# acdcconverter.net
KiCad netlist of a schematic drawn in EAGLE
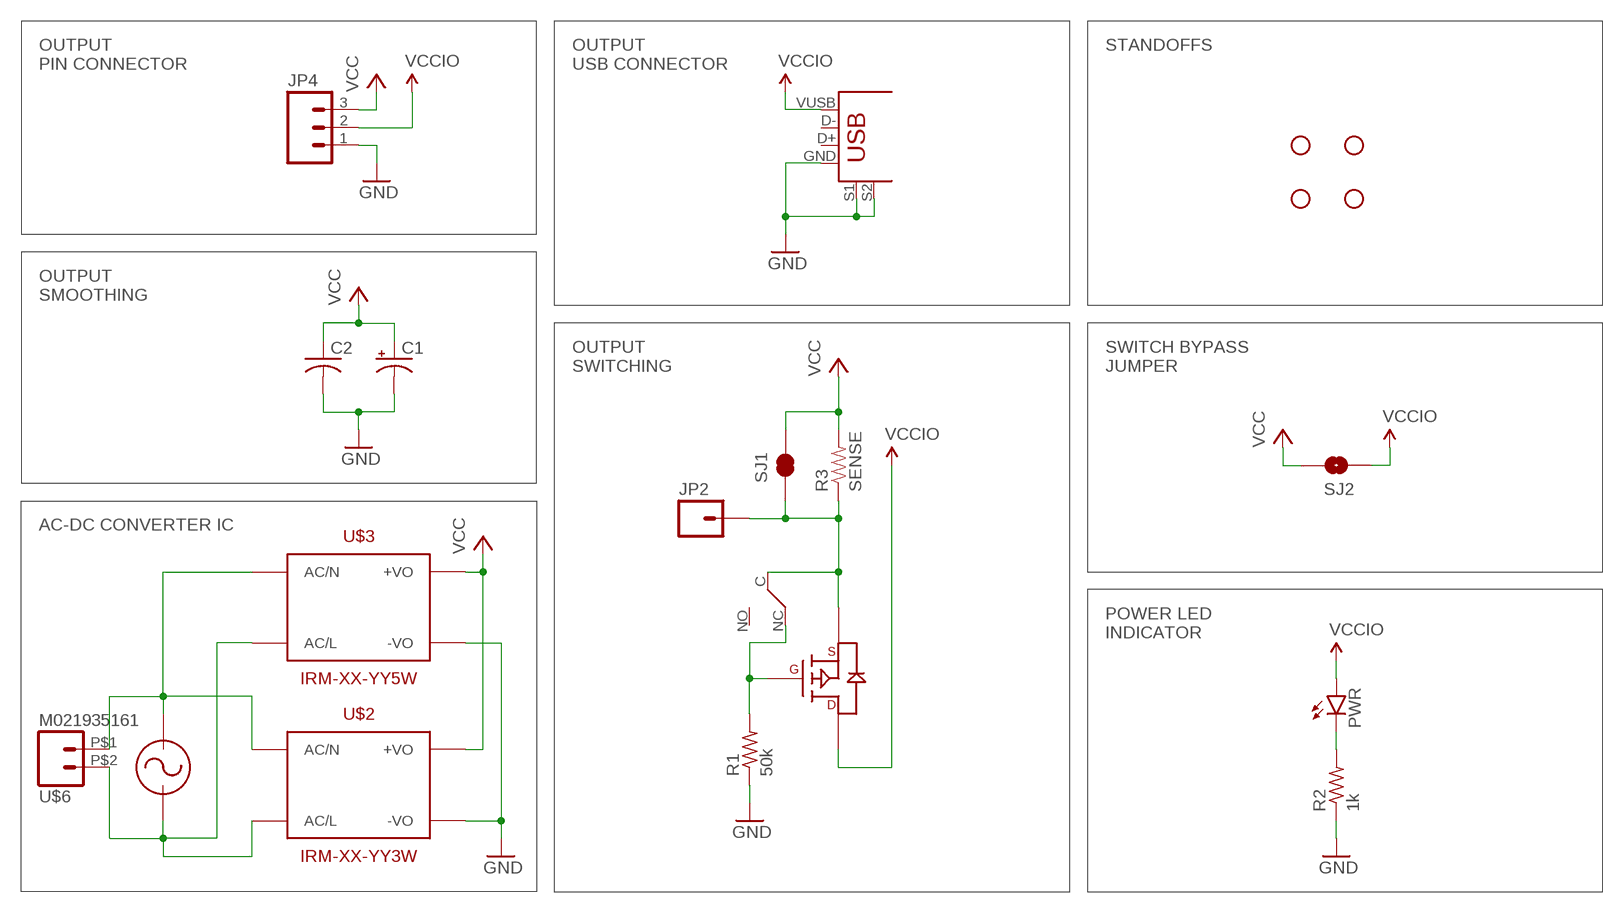
[diagram p0: schematic, sheet 1]

(export (version "E")
  (design (tool "Eeschema 10.0.6"))
  (components
    (comp (ref "C1")
      (value "CPOL-USE2-5")
      (footprint "eagle-import:E2-5")
      (libsource (lib "eagle-import") (part "CPOL-USE2-5"))
    )
    (comp (ref "C2")
      (value "C-USC0603")
      (footprint "eagle-import:C0603")
      (libsource (lib "eagle-import") (part "C-USC0603"))
    )
    (comp (ref "JP2")
      (value "M01PTH")
      (footprint "eagle-import:1X01")
      (libsource (lib "eagle-import") (part "M01PTH"))
    )
    (comp (ref "JP4")
      (value "M03PTH")
      (footprint "eagle-import:1X03")
      (libsource (lib "eagle-import") (part "M03PTH"))
    )
    (comp (ref "PWR")
      (value "LED0603")
      (footprint "eagle-import:LED-0603")
      (libsource (lib "eagle-import") (part "LED0603"))
    )
    (comp (ref "R1")
      (value "50k")
      (footprint "eagle-import:R0603")
      (libsource (lib "eagle-import") (part "R-US_R0603"))
    )
    (comp (ref "R2")
      (value "1k")
      (footprint "eagle-import:R0603")
      (libsource (lib "eagle-import") (part "R-US_R0603"))
    )
    (comp (ref "R3")
      (value "SENSE")
      (footprint "eagle-import:0805")
      (libsource (lib "eagle-import") (part "RESISTOR0805-RES"))
    )
    (comp (ref "SJ1")
      (value "JUMPER-PAD-2-NC_BY_TRACE")
      (footprint "eagle-import:PAD-JUMPER-2-NC_BY_TRACE_YES_SILK")
      (libsource (lib "eagle-import") (part "JUMPER-PAD-2-NC_BY_TRACE"))
    )
    (comp (ref "SJ2")
      (value "SOLDERJUMPERNO")
      (footprint "eagle-import:SJ_2S-NO")
      (libsource (lib "eagle-import") (part "SOLDERJUMPERNO"))
    )
    (comp (ref "STANDOFF1")
      (value "STAND-OFF")
      (footprint "eagle-import:STAND-OFF")
      (libsource (lib "eagle-import") (part "STAND-OFF"))
    )
    (comp (ref "STANDOFF2")
      (value "STAND-OFF")
      (footprint "eagle-import:STAND-OFF")
      (libsource (lib "eagle-import") (part "STAND-OFF"))
    )
    (comp (ref "STANDOFF3")
      (value "STAND-OFF")
      (footprint "eagle-import:STAND-OFF")
      (libsource (lib "eagle-import") (part "STAND-OFF"))
    )
    (comp (ref "STANDOFF4")
      (value "STAND-OFF")
      (footprint "eagle-import:STAND-OFF")
      (libsource (lib "eagle-import") (part "STAND-OFF"))
    )
    (comp (ref "U$1")
      (value "AC-CONNECTOR770W-X2")
      (footprint "eagle-import:770W-X2")
      (libsource (lib "eagle-import") (part "AC-CONNECTOR770W-X2"))
    )
    (comp (ref "U$2")
      (value "IRM-XX-YY3W")
      (footprint "eagle-import:IRM-03-YY")
      (libsource (lib "eagle-import") (part "IRM-XX-YY3W"))
    )
    (comp (ref "U$3")
      (value "IRM-XX-YY5W")
      (footprint "eagle-import:IRM-05-YY")
      (libsource (lib "eagle-import") (part "IRM-XX-YY5W"))
    )
    (comp (ref "U$5")
      (value "SWITCH-SPDT")
      (footprint "eagle-import:SWITCH-1825232-1")
      (libsource (lib "eagle-import") (part "SWITCH-SPDT"))
    )
    (comp (ref "U$6")
      (value "M021935161")
      (footprint "eagle-import:M02-1935161")
      (libsource (lib "eagle-import") (part "M021935161"))
    )
    (comp (ref "U$7")
      (value "USB-FEMALE")
      (footprint "eagle-import:FOXCONN-113N-USB-A-FEMALE")
      (libsource (lib "eagle-import") (part "USB-FEMALE"))
    )
    (comp (ref "U$8")
      (value "MOSFET-PDMG2305UX")
      (footprint "eagle-import:SOT23-3")
      (libsource (lib "eagle-import") (part "MOSFET-PDMG2305UX"))
    )
  )
  (nets
    (net (code "1") (name "GND") (class "Default")
      (node (ref "C1") (pin "-") (pinfunction "-_-") (pintype "passive"))
      (node (ref "C2") (pin "2") (pinfunction "2_2") (pintype "passive"))
      (node (ref "JP4") (pin "1") (pinfunction "1_1") (pintype "passive"))
      (node (ref "R1") (pin "1") (pinfunction "1_1") (pintype "passive"))
      (node (ref "R2") (pin "1") (pinfunction "1_1") (pintype "passive"))
      (node (ref "U$2") (pin "-VO") (pinfunction "-VO_-VO") (pintype "power_in"))
      (node (ref "U$3") (pin "-VO") (pinfunction "-VO_-VO") (pintype "power_in"))
      (node (ref "U$7") (pin "GND") (pinfunction "GND_GND") (pintype "bidirectional"))
      (node (ref "U$7") (pin "S1") (pinfunction "S1_S1") (pintype "bidirectional"))
      (node (ref "U$7") (pin "S2") (pinfunction "S2_S2") (pintype "bidirectional"))
    )
    (net (code "2") (name "Net-(PWR-PadC)") (class "Default")
      (node (ref "PWR") (pin "C") (pinfunction "C_C") (pintype "passive"))
      (node (ref "R2") (pin "2") (pinfunction "2_2") (pintype "passive"))
    )
    (net (code "3") (name "Net-(U$1-AC1)") (class "Default")
      (node (ref "U$1") (pin "P$1") (pinfunction "AC1_P$1") (pintype "power_in"))
      (node (ref "U$2") (pin "AC/L") (pinfunction "AC/L_AC/L") (pintype "power_in"))
      (node (ref "U$3") (pin "AC/L") (pinfunction "AC/L_AC/L") (pintype "power_in"))
      (node (ref "U$6") (pin "P$2") (pinfunction "2_P$2") (pintype "passive"))
    )
    (net (code "4") (name "Net-(U$1-AC2)") (class "Default")
      (node (ref "U$1") (pin "P$2") (pinfunction "AC2_P$2") (pintype "power_in"))
      (node (ref "U$2") (pin "AC/N") (pinfunction "AC/N_AC/N") (pintype "power_in"))
      (node (ref "U$3") (pin "AC/N") (pinfunction "AC/N_AC/N") (pintype "power_in"))
      (node (ref "U$6") (pin "P$1") (pinfunction "1_P$1") (pintype "passive"))
    )
    (net (code "5") (name "Net-(U$8-GATE)") (class "Default")
      (node (ref "R1") (pin "2") (pinfunction "2_2") (pintype "passive"))
      (node (ref "U$5") (pin "NC") (pinfunction "NC_NC") (pintype "bidirectional"))
      (node (ref "U$8") (pin "3") (pinfunction "GATE_3") (pintype "bidirectional"))
    )
    (net (code "6") (name "Net-(U$8-SOURCE)") (class "Default")
      (node (ref "JP2") (pin "1") (pinfunction "1_1") (pintype "passive"))
      (node (ref "R3") (pin "1") (pinfunction "1_1") (pintype "passive"))
      (node (ref "SJ1") (pin "1") (pinfunction "1_1") (pintype "passive"))
      (node (ref "U$5") (pin "C") (pinfunction "C_C") (pintype "bidirectional"))
      (node (ref "U$8") (pin "1") (pinfunction "SOURCE_1") (pintype "bidirectional"))
    )
    (net (code "7") (name "VCC") (class "Default")
      (node (ref "C1") (pin "+") (pinfunction "+_+") (pintype "passive"))
      (node (ref "C2") (pin "1") (pinfunction "1_1") (pintype "passive"))
      (node (ref "JP4") (pin "3") (pinfunction "3_3") (pintype "passive"))
      (node (ref "R3") (pin "2") (pinfunction "2_2") (pintype "passive"))
      (node (ref "SJ1") (pin "2") (pinfunction "2_2") (pintype "passive"))
      (node (ref "SJ2") (pin "2") (pinfunction "2_2") (pintype "passive"))
      (node (ref "U$2") (pin "+VO") (pinfunction "+VO_+VO") (pintype "power_in"))
      (node (ref "U$3") (pin "+VO") (pinfunction "+VO_+VO") (pintype "power_in"))
    )
    (net (code "8") (name "VCCIO") (class "Default")
      (node (ref "JP4") (pin "2") (pinfunction "2_2") (pintype "passive"))
      (node (ref "PWR") (pin "A") (pinfunction "A_A") (pintype "passive"))
      (node (ref "SJ2") (pin "1") (pinfunction "1_1") (pintype "passive"))
      (node (ref "U$7") (pin "VUSB") (pinfunction "VUSB_VUSB") (pintype "bidirectional"))
      (node (ref "U$8") (pin "2") (pinfunction "DRAIN_2") (pintype "bidirectional"))
    )
    (net (code "9") (name "unconnected-(U$5-PadNO)") (class "Default")
      (node (ref "U$5") (pin "NO") (pinfunction "NO_NO") (pintype "bidirectional"))
    )
    (net (code "10") (name "unconnected-(U$7-PadD+)") (class "Default")
      (node (ref "U$7") (pin "D+") (pinfunction "D+_D+") (pintype "bidirectional"))
    )
    (net (code "11") (name "unconnected-(U$7-PadD-)") (class "Default")
      (node (ref "U$7") (pin "D-") (pinfunction "D-_D-") (pintype "bidirectional"))
    )
  )
)
